# stm32h743.net
KiCad netlist of a schematic drawn in Altium Designer
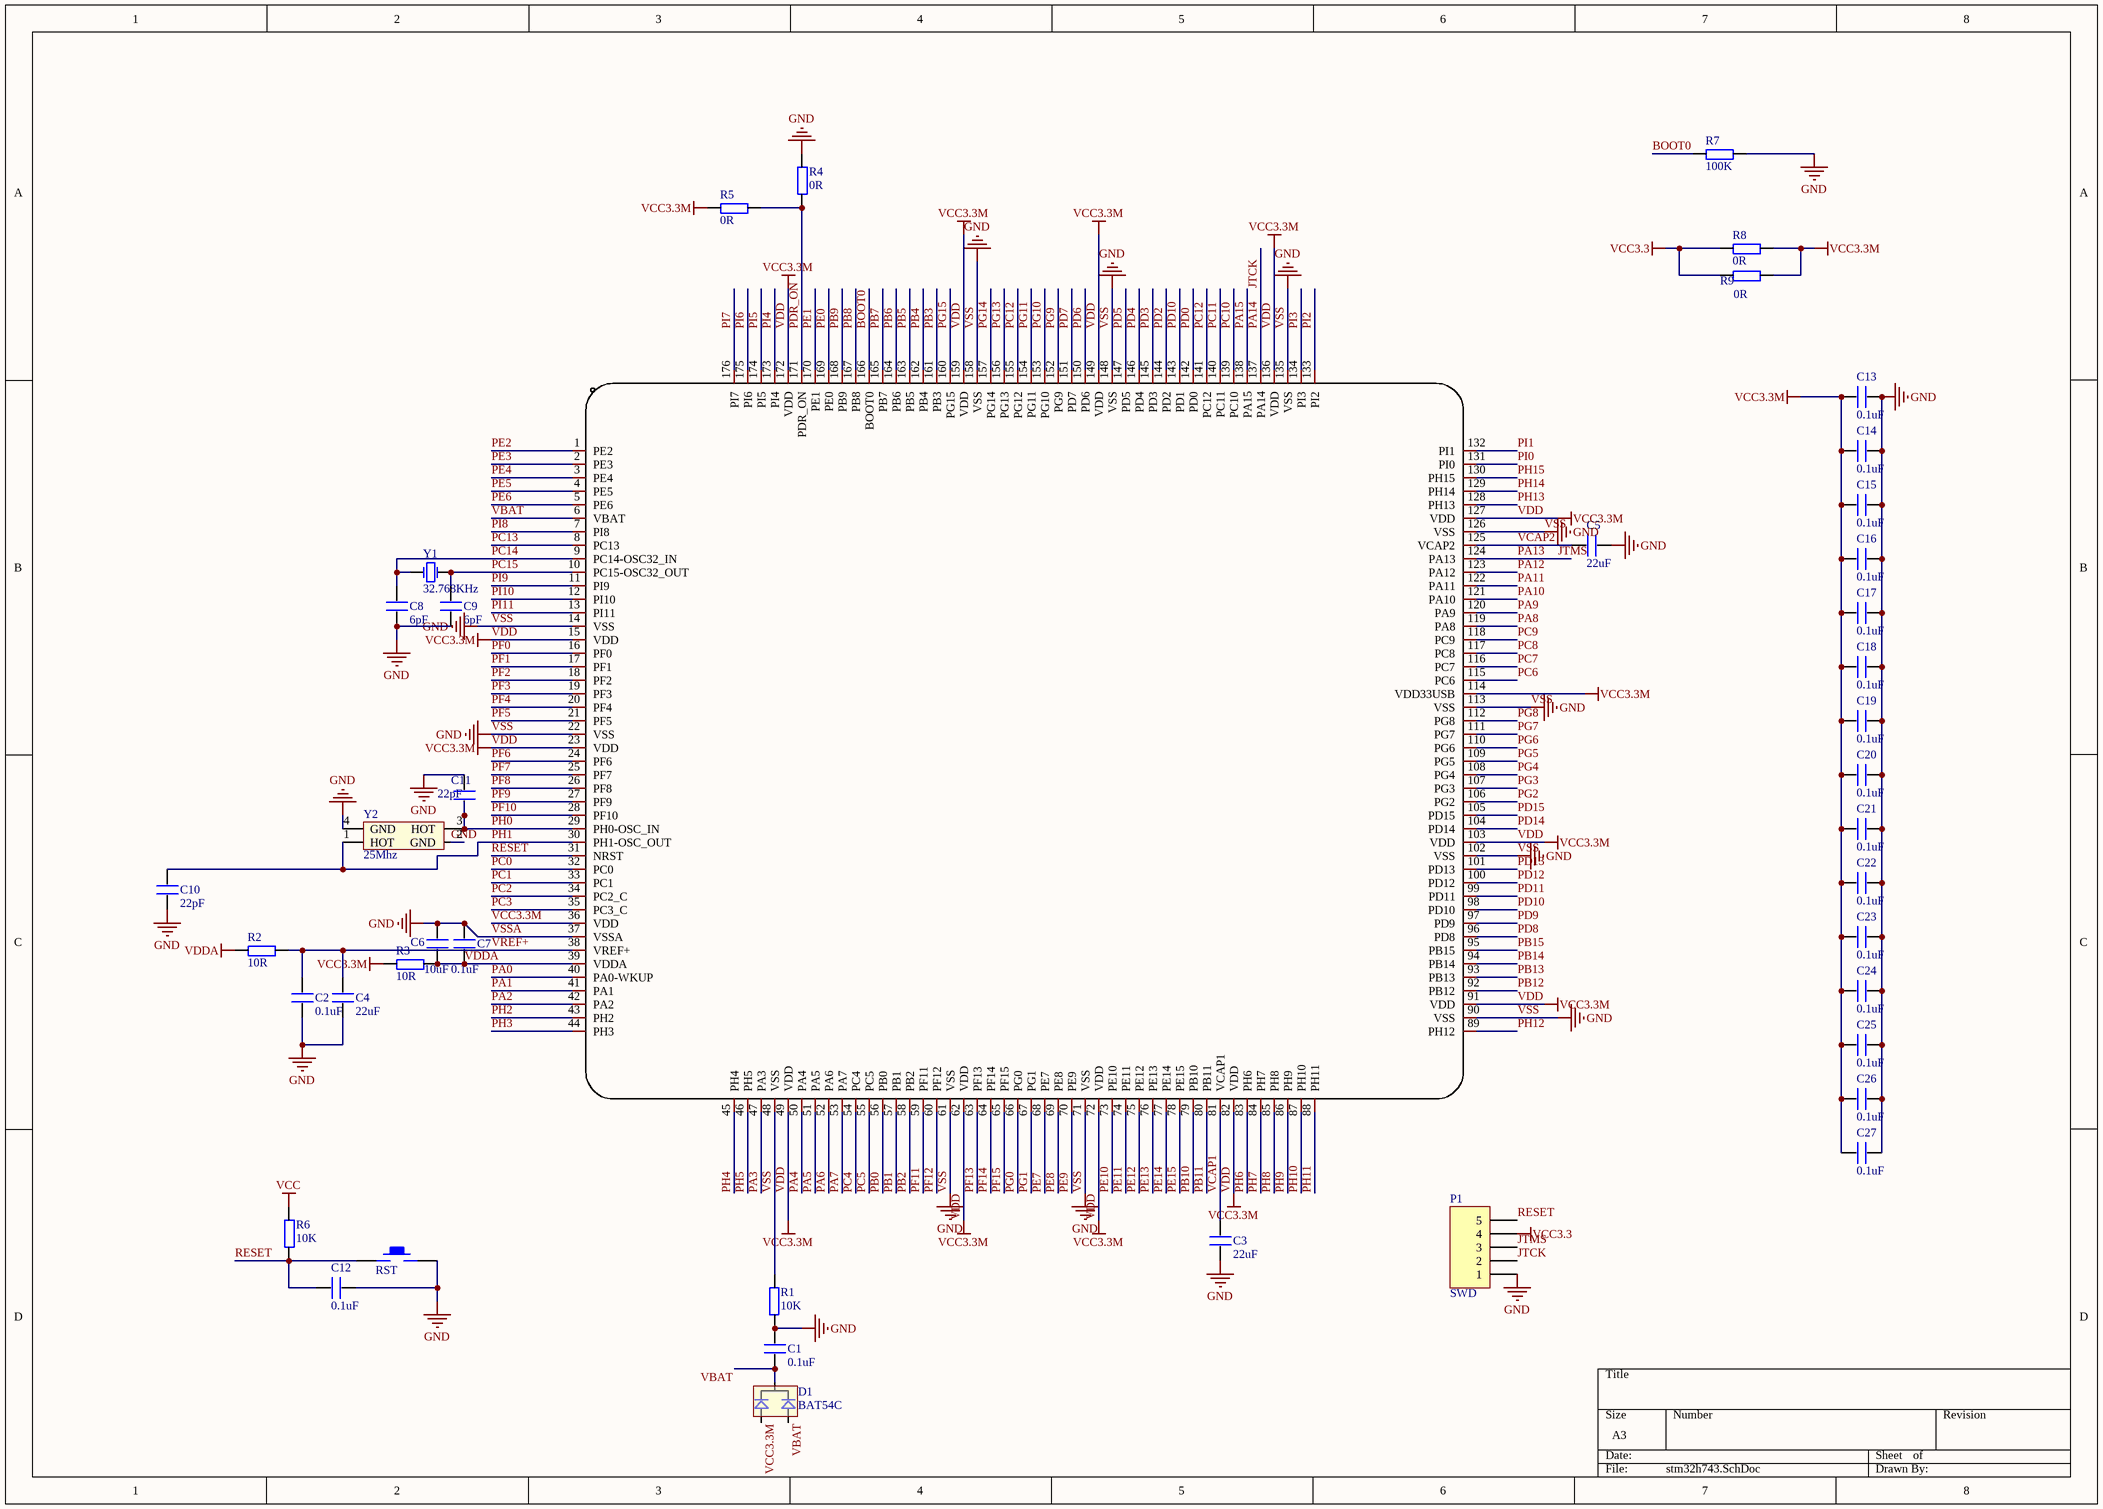
[diagram p0: stm32h743.SchDoc]

(export (version "E")
  (design (tool "Eeschema 10.0.6"))
  (components
    (comp (ref "C1") (value "0.1uF") (footprint "0402") (libsource (lib "STM32H743核心板封装库") (part "C")))
    (comp (ref "C2") (value "0.1uF") (footprint "0402") (libsource (lib "STM32H743核心板封装库") (part "C")))
    (comp (ref "C3") (value "22uF") (footprint "0402") (libsource (lib "STM32H743核心板封装库") (part "C")))
    (comp (ref "C4") (value "22uF") (footprint "0402") (libsource (lib "STM32H743核心板封装库") (part "C")))
    (comp (ref "C5") (value "22uF") (footprint "0402") (libsource (lib "STM32H743核心板封装库") (part "C")))
    (comp (ref "C6") (value "10uF") (footprint "0402") (libsource (lib "STM32H743核心板封装库") (part "C")))
    (comp (ref "C7") (value "0.1uF") (footprint "0402") (libsource (lib "STM32H743核心板封装库") (part "C")))
    (comp (ref "C8") (value "6pF") (footprint "0402") (libsource (lib "STM32H743核心板封装库") (part "C_7")))
    (comp (ref "C9") (value "6pF") (footprint "0402") (libsource (lib "STM32H743核心板封装库") (part "C_7")))
    (comp (ref "C10") (value "22pF") (footprint "0402") (libsource (lib "STM32H743核心板封装库") (part "C")))
    (comp (ref "C11") (value "22pF") (footprint "0402") (libsource (lib "STM32H743核心板封装库") (part "C")))
    (comp (ref "C12") (value "0.1uF") (footprint "0402") (libsource (lib "STM32H743核心板封装库") (part "C")))
    (comp (ref "C13") (value "0.1uF") (footprint "0402") (libsource (lib "STM32H743核心板封装库") (part "C")))
    (comp (ref "C14") (value "0.1uF") (footprint "0402") (libsource (lib "STM32H743核心板封装库") (part "C")))
    (comp (ref "C15") (value "0.1uF") (footprint "0402") (libsource (lib "STM32H743核心板封装库") (part "C")))
    (comp (ref "C16") (value "0.1uF") (footprint "0402") (libsource (lib "STM32H743核心板封装库") (part "C")))
    (comp (ref "C17") (value "0.1uF") (footprint "0402") (libsource (lib "STM32H743核心板封装库") (part "C")))
    (comp (ref "C18") (value "0.1uF") (footprint "0402") (libsource (lib "STM32H743核心板封装库") (part "C")))
    (comp (ref "C19") (value "0.1uF") (footprint "0402") (libsource (lib "STM32H743核心板封装库") (part "C")))
    (comp (ref "C20") (value "0.1uF") (footprint "0402") (libsource (lib "STM32H743核心板封装库") (part "C")))
    (comp (ref "C21") (value "0.1uF") (footprint "0402") (libsource (lib "STM32H743核心板封装库") (part "C")))
    (comp (ref "C22") (value "0.1uF") (footprint "0402") (libsource (lib "STM32H743核心板封装库") (part "C")))
    (comp (ref "C23") (value "0.1uF") (footprint "0402") (libsource (lib "STM32H743核心板封装库") (part "C")))
    (comp (ref "C24") (value "0.1uF") (footprint "0402") (libsource (lib "STM32H743核心板封装库") (part "C")))
    (comp (ref "C25") (value "0.1uF") (footprint "0402") (libsource (lib "STM32H743核心板封装库") (part "C")))
    (comp (ref "C26") (value "0.1uF") (footprint "0402") (libsource (lib "STM32H743核心板封装库") (part "C")))
    (comp (ref "C27") (value "0.1uF") (footprint "0402") (libsource (lib "STM32H743核心板封装库") (part "C")))
    (comp (ref "D1")
      (value "BAT54C")
      (footprint "SOT-23")
      (description "双肖特基二极管")
      (libsource (lib "STM32H743核心板封装库") (part "BAT54C"))
    )
    (comp (ref "P1")
      (value "SWD")
      (footprint "HDR1X5")
      (description "Header, 5-Pin")
      (fields (field (name "PUBLISHER") "Altium Limited"))
      (libsource (lib "STM32H743核心板封装库") (part "Header 5"))
    )
    (comp (ref "R1") (value "10K") (footprint "0402") (libsource (lib "STM32H743核心板封装库") (part "R")))
    (comp (ref "R2") (value "10R") (footprint "0402") (libsource (lib "STM32H743核心板封装库") (part "R")))
    (comp (ref "R3") (value "10R") (footprint "0402") (libsource (lib "STM32H743核心板封装库") (part "R")))
    (comp (ref "R4") (value "0R") (footprint "0402") (libsource (lib "STM32H743核心板封装库") (part "R")))
    (comp (ref "R5") (value "0R") (footprint "0402") (libsource (lib "STM32H743核心板封装库") (part "R")))
    (comp (ref "R6") (value "10K") (footprint "0402") (libsource (lib "STM32H743核心板封装库") (part "R")))
    (comp (ref "R7") (value "100K") (footprint "0402") (libsource (lib "STM32H743核心板封装库") (part "R")))
    (comp (ref "R8") (value "0R") (footprint "0402") (libsource (lib "STM32H743核心板封装库") (part "R")))
    (comp (ref "R9") (value "0R") (footprint "0402") (libsource (lib "STM32H743核心板封装库") (part "R")))
    (comp (ref "RST")
      (value "KEY_M")
      (footprint "KEY_SOP324225")
      (libsource (lib "STM32H743核心板封装库") (part "KEY_M"))
    )
    (comp (ref "U1")
      (value "STM32H743IIT6")
      (footprint "LQFP176")
      (fields (field (name "MANUFACTURER") "ST(意法半导体)"))
      (libsource (lib "altium-import") (part "root_0_STM32H743IIT6_"))
    )
    (comp (ref "Y1")
      (value "32.768KHz")
      (footprint "XTAL3215")
      (description "普通晶振")
      (fields (field (name "PUBLISHER") "Altium Limited"))
      (libsource (lib "STM32H743核心板封装库") (part "XTAL"))
    )
    (comp (ref "Y2")
      (value "25Mhz")
      (footprint "XTAL3225")
      (description "3225贴片无源晶振")
      (libsource (lib "STM32H743核心板封装库") (part "XTAL_3225"))
    )
  )
  (nets
    (net (code "1") (name "/BOOT0") (class "Default")
      (node (ref "R7") (pin "1") (pintype "passive"))
      (node (ref "U1") (pin "166") (pinfunction "BOOT0_166") (pintype "passive"))
    )
    (net (code "2") (name "/JTCK") (class "Default")
      (node (ref "P1") (pin "2") (pinfunction "2_2") (pintype "passive"))
      (node (ref "U1") (pin "137") (pinfunction "PA14_137") (pintype "passive"))
    )
    (net (code "3") (name "/JTMS") (class "Default")
      (node (ref "P1") (pin "3") (pinfunction "3_3") (pintype "passive"))
      (node (ref "U1") (pin "124") (pinfunction "PA13_124") (pintype "passive"))
    )
    (net (code "4") (name "/PA0") (class "Default")
      (node (ref "U1") (pin "40") (pinfunction "PA0-WKUP_40") (pintype "passive"))
    )
    (net (code "5") (name "/PA1") (class "Default")
      (node (ref "U1") (pin "41") (pinfunction "PA1_41") (pintype "passive"))
    )
    (net (code "6") (name "/PA2") (class "Default")
      (node (ref "U1") (pin "42") (pinfunction "PA2_42") (pintype "passive"))
    )
    (net (code "7") (name "/PA3") (class "Default")
      (node (ref "U1") (pin "47") (pinfunction "PA3_47") (pintype "passive"))
    )
    (net (code "8") (name "/PA4") (class "Default")
      (node (ref "U1") (pin "50") (pinfunction "PA4_50") (pintype "passive"))
    )
    (net (code "9") (name "/PA5") (class "Default")
      (node (ref "U1") (pin "51") (pinfunction "PA5_51") (pintype "passive"))
    )
    (net (code "10") (name "/PA6") (class "Default")
      (node (ref "U1") (pin "52") (pinfunction "PA6_52") (pintype "passive"))
    )
    (net (code "11") (name "/PA7") (class "Default")
      (node (ref "U1") (pin "53") (pinfunction "PA7_53") (pintype "passive"))
    )
    (net (code "12") (name "/PA8") (class "Default")
      (node (ref "U1") (pin "119") (pinfunction "PA8_119") (pintype "passive"))
    )
    (net (code "13") (name "/PA9") (class "Default")
      (node (ref "U1") (pin "120") (pinfunction "PA9_120") (pintype "passive"))
    )
    (net (code "14") (name "/PA10") (class "Default")
      (node (ref "U1") (pin "121") (pinfunction "PA10_121") (pintype "passive"))
    )
    (net (code "15") (name "/PA11") (class "Default")
      (node (ref "U1") (pin "122") (pinfunction "PA11_122") (pintype "passive"))
    )
    (net (code "16") (name "/PA12") (class "Default")
      (node (ref "U1") (pin "123") (pinfunction "PA12_123") (pintype "passive"))
    )
    (net (code "17") (name "/PA15") (class "Default")
      (node (ref "U1") (pin "138") (pinfunction "PA15_138") (pintype "passive"))
    )
    (net (code "18") (name "/PB0") (class "Default")
      (node (ref "U1") (pin "56") (pinfunction "PB0_56") (pintype "passive"))
    )
    (net (code "19") (name "/PB1") (class "Default")
      (node (ref "U1") (pin "57") (pinfunction "PB1_57") (pintype "passive"))
    )
    (net (code "20") (name "/PB2") (class "Default")
      (node (ref "U1") (pin "58") (pinfunction "PB2_58") (pintype "passive"))
    )
    (net (code "21") (name "/PB3") (class "Default")
      (node (ref "U1") (pin "161") (pinfunction "PB3_161") (pintype "passive"))
    )
    (net (code "22") (name "/PB4") (class "Default")
      (node (ref "U1") (pin "162") (pinfunction "PB4_162") (pintype "passive"))
    )
    (net (code "23") (name "/PB5") (class "Default")
      (node (ref "U1") (pin "163") (pinfunction "PB5_163") (pintype "passive"))
    )
    (net (code "24") (name "/PB6") (class "Default")
      (node (ref "U1") (pin "164") (pinfunction "PB6_164") (pintype "passive"))
    )
    (net (code "25") (name "/PB7") (class "Default")
      (node (ref "U1") (pin "165") (pinfunction "PB7_165") (pintype "passive"))
    )
    (net (code "26") (name "/PB8") (class "Default")
      (node (ref "U1") (pin "167") (pinfunction "PB8_167") (pintype "passive"))
    )
    (net (code "27") (name "/PB9") (class "Default")
      (node (ref "U1") (pin "168") (pinfunction "PB9_168") (pintype "passive"))
    )
    (net (code "28") (name "/PB10") (class "Default")
      (node (ref "U1") (pin "79") (pinfunction "PB10_79") (pintype "passive"))
    )
    (net (code "29") (name "/PB11") (class "Default")
      (node (ref "U1") (pin "80") (pinfunction "PB11_80") (pintype "passive"))
    )
    (net (code "30") (name "/PB12") (class "Default")
      (node (ref "U1") (pin "92") (pinfunction "PB12_92") (pintype "passive"))
    )
    (net (code "31") (name "/PB13") (class "Default")
      (node (ref "U1") (pin "93") (pinfunction "PB13_93") (pintype "passive"))
    )
    (net (code "32") (name "/PB14") (class "Default")
      (node (ref "U1") (pin "94") (pinfunction "PB14_94") (pintype "passive"))
    )
    (net (code "33") (name "/PB15") (class "Default")
      (node (ref "U1") (pin "95") (pinfunction "PB15_95") (pintype "passive"))
    )
    (net (code "34") (name "/PC0") (class "Default")
      (node (ref "U1") (pin "32") (pinfunction "PC0_32") (pintype "passive"))
    )
    (net (code "35") (name "/PC1") (class "Default")
      (node (ref "U1") (pin "33") (pinfunction "PC1_33") (pintype "passive"))
    )
    (net (code "36") (name "/PC2") (class "Default")
      (node (ref "U1") (pin "34") (pinfunction "PC2_C_34") (pintype "passive"))
    )
    (net (code "37") (name "/PC3") (class "Default")
      (node (ref "U1") (pin "35") (pinfunction "PC3_C_35") (pintype "passive"))
    )
    (net (code "38") (name "/PC4") (class "Default")
      (node (ref "U1") (pin "54") (pinfunction "PC4_54") (pintype "passive"))
    )
    (net (code "39") (name "/PC5") (class "Default")
      (node (ref "U1") (pin "55") (pinfunction "PC5_55") (pintype "passive"))
    )
    (net (code "40") (name "/PC6") (class "Default")
      (node (ref "U1") (pin "115") (pinfunction "PC6_115") (pintype "passive"))
    )
    (net (code "41") (name "/PC7") (class "Default")
      (node (ref "U1") (pin "116") (pinfunction "PC7_116") (pintype "passive"))
    )
    (net (code "42") (name "/PC8") (class "Default")
      (node (ref "U1") (pin "117") (pinfunction "PC8_117") (pintype "passive"))
    )
    (net (code "43") (name "/PC9") (class "Default")
      (node (ref "U1") (pin "118") (pinfunction "PC9_118") (pintype "passive"))
    )
    (net (code "44") (name "/PC10") (class "Default")
      (node (ref "U1") (pin "139") (pinfunction "PC10_139") (pintype "passive"))
    )
    (net (code "45") (name "/PC11") (class "Default")
      (node (ref "U1") (pin "140") (pinfunction "PC11_140") (pintype "passive"))
    )
    (net (code "46") (name "/PC12") (class "Default")
      (node (ref "U1") (pin "141") (pinfunction "PC12_141") (pintype "passive"))
      (node (ref "U1") (pin "155") (pinfunction "PG12_155") (pintype "passive"))
    )
    (net (code "47") (name "/PC13") (class "Default")
      (node (ref "U1") (pin "8") (pinfunction "PC13_8") (pintype "passive"))
    )
    (net (code "48") (name "/PC14") (class "Default")
      (node (ref "C8") (pin "2") (pintype "passive"))
      (node (ref "U1") (pin "9") (pinfunction "PC14-OSC32_IN_9") (pintype "passive"))
      (node (ref "Y1") (pin "1") (pinfunction "OSC1_1") (pintype "passive"))
    )
    (net (code "49") (name "/PC15") (class "Default")
      (node (ref "C9") (pin "2") (pintype "passive"))
      (node (ref "U1") (pin "10") (pinfunction "PC15-OSC32_OUT_10") (pintype "passive"))
      (node (ref "Y1") (pin "2") (pinfunction "OSC2_2") (pintype "passive"))
    )
    (net (code "50") (name "/PD0") (class "Default")
      (node (ref "U1") (pin "142") (pinfunction "PD0_142") (pintype "passive"))
    )
    (net (code "51") (name "/PD2") (class "Default")
      (node (ref "U1") (pin "144") (pinfunction "PD2_144") (pintype "passive"))
    )
    (net (code "52") (name "/PD3") (class "Default")
      (node (ref "U1") (pin "145") (pinfunction "PD3_145") (pintype "passive"))
    )
    (net (code "53") (name "/PD4") (class "Default")
      (node (ref "U1") (pin "146") (pinfunction "PD4_146") (pintype "passive"))
    )
    (net (code "54") (name "/PD5") (class "Default")
      (node (ref "U1") (pin "147") (pinfunction "PD5_147") (pintype "passive"))
    )
    (net (code "55") (name "/PD6") (class "Default")
      (node (ref "U1") (pin "150") (pinfunction "PD6_150") (pintype "passive"))
    )
    (net (code "56") (name "/PD7") (class "Default")
      (node (ref "U1") (pin "151") (pinfunction "PD7_151") (pintype "passive"))
    )
    (net (code "57") (name "/PD8") (class "Default")
      (node (ref "U1") (pin "96") (pinfunction "PD8_96") (pintype "passive"))
    )
    (net (code "58") (name "/PD9") (class "Default")
      (node (ref "U1") (pin "97") (pinfunction "PD9_97") (pintype "passive"))
    )
    (net (code "59") (name "/PD10") (class "Default")
      (node (ref "U1") (pin "143") (pinfunction "PD1_143") (pintype "passive"))
      (node (ref "U1") (pin "98") (pinfunction "PD10_98") (pintype "passive"))
    )
    (net (code "60") (name "/PD11") (class "Default")
      (node (ref "U1") (pin "99") (pinfunction "PD11_99") (pintype "passive"))
    )
    (net (code "61") (name "/PD12") (class "Default")
      (node (ref "U1") (pin "100") (pinfunction "PD12_100") (pintype "passive"))
    )
    (net (code "62") (name "/PD13") (class "Default")
      (node (ref "U1") (pin "101") (pinfunction "PD13_101") (pintype "passive"))
    )
    (net (code "63") (name "/PD14") (class "Default")
      (node (ref "U1") (pin "104") (pinfunction "PD14_104") (pintype "passive"))
    )
    (net (code "64") (name "/PD15") (class "Default")
      (node (ref "U1") (pin "105") (pinfunction "PD15_105") (pintype "passive"))
    )
    (net (code "65") (name "/PDR_ON") (class "Default")
      (node (ref "R4") (pin "1") (pintype "passive"))
      (node (ref "R5") (pin "2") (pintype "passive"))
      (node (ref "U1") (pin "171") (pinfunction "PDR_ON_171") (pintype "passive"))
    )
    (net (code "66") (name "/PE0") (class "Default")
      (node (ref "U1") (pin "169") (pinfunction "PE0_169") (pintype "passive"))
    )
    (net (code "67") (name "/PE1") (class "Default")
      (node (ref "U1") (pin "170") (pinfunction "PE1_170") (pintype "passive"))
    )
    (net (code "68") (name "/PE2") (class "Default")
      (node (ref "U1") (pin "1") (pinfunction "PE2_1") (pintype "passive"))
    )
    (net (code "69") (name "/PE3") (class "Default")
      (node (ref "U1") (pin "2") (pinfunction "PE3_2") (pintype "passive"))
    )
    (net (code "70") (name "/PE4") (class "Default")
      (node (ref "U1") (pin "3") (pinfunction "PE4_3") (pintype "passive"))
    )
    (net (code "71") (name "/PE5") (class "Default")
      (node (ref "U1") (pin "4") (pinfunction "PE5_4") (pintype "passive"))
    )
    (net (code "72") (name "/PE6") (class "Default")
      (node (ref "U1") (pin "5") (pinfunction "PE6_5") (pintype "passive"))
    )
    (net (code "73") (name "/PE7") (class "Default")
      (node (ref "U1") (pin "68") (pinfunction "PE7_68") (pintype "passive"))
    )
    (net (code "74") (name "/PE8") (class "Default")
      (node (ref "U1") (pin "69") (pinfunction "PE8_69") (pintype "passive"))
    )
    (net (code "75") (name "/PE9") (class "Default")
      (node (ref "U1") (pin "70") (pinfunction "PE9_70") (pintype "passive"))
    )
    (net (code "76") (name "/PE10") (class "Default")
      (node (ref "U1") (pin "73") (pinfunction "PE10_73") (pintype "passive"))
    )
    (net (code "77") (name "/PE11") (class "Default")
      (node (ref "U1") (pin "74") (pinfunction "PE11_74") (pintype "passive"))
    )
    (net (code "78") (name "/PE12") (class "Default")
      (node (ref "U1") (pin "75") (pinfunction "PE12_75") (pintype "passive"))
    )
    (net (code "79") (name "/PE13") (class "Default")
      (node (ref "U1") (pin "76") (pinfunction "PE13_76") (pintype "passive"))
    )
    (net (code "80") (name "/PE14") (class "Default")
      (node (ref "U1") (pin "77") (pinfunction "PE14_77") (pintype "passive"))
    )
    (net (code "81") (name "/PE15") (class "Default")
      (node (ref "U1") (pin "78") (pinfunction "PE15_78") (pintype "passive"))
    )
    (net (code "82") (name "/PF0") (class "Default")
      (node (ref "U1") (pin "16") (pinfunction "PF0_16") (pintype "passive"))
    )
    (net (code "83") (name "/PF1") (class "Default")
      (node (ref "U1") (pin "17") (pinfunction "PF1_17") (pintype "passive"))
    )
    (net (code "84") (name "/PF2") (class "Default")
      (node (ref "U1") (pin "18") (pinfunction "PF2_18") (pintype "passive"))
    )
    (net (code "85") (name "/PF3") (class "Default")
      (node (ref "U1") (pin "19") (pinfunction "PF3_19") (pintype "passive"))
    )
    (net (code "86") (name "/PF4") (class "Default")
      (node (ref "U1") (pin "20") (pinfunction "PF4_20") (pintype "passive"))
    )
    (net (code "87") (name "/PF5") (class "Default")
      (node (ref "U1") (pin "21") (pinfunction "PF5_21") (pintype "passive"))
    )
    (net (code "88") (name "/PF6") (class "Default")
      (node (ref "U1") (pin "24") (pinfunction "PF6_24") (pintype "passive"))
    )
    (net (code "89") (name "/PF7") (class "Default")
      (node (ref "U1") (pin "25") (pinfunction "PF7_25") (pintype "passive"))
    )
    (net (code "90") (name "/PF8") (class "Default")
      (node (ref "U1") (pin "26") (pinfunction "PF8_26") (pintype "passive"))
    )
    (net (code "91") (name "/PF9") (class "Default")
      (node (ref "U1") (pin "27") (pinfunction "PF9_27") (pintype "passive"))
    )
    (net (code "92") (name "/PF10") (class "Default")
      (node (ref "U1") (pin "28") (pinfunction "PF10_28") (pintype "passive"))
    )
    (net (code "93") (name "/PF11") (class "Default")
      (node (ref "U1") (pin "59") (pinfunction "PF11_59") (pintype "passive"))
    )
    (net (code "94") (name "/PF12") (class "Default")
      (node (ref "U1") (pin "60") (pinfunction "PF12_60") (pintype "passive"))
    )
    (net (code "95") (name "/PF13") (class "Default")
      (node (ref "U1") (pin "63") (pinfunction "PF13_63") (pintype "passive"))
    )
    (net (code "96") (name "/PF14") (class "Default")
      (node (ref "U1") (pin "64") (pinfunction "PF14_64") (pintype "passive"))
    )
    (net (code "97") (name "/PF15") (class "Default")
      (node (ref "U1") (pin "65") (pinfunction "PF15_65") (pintype "passive"))
    )
    (net (code "98") (name "/PG0") (class "Default")
      (node (ref "U1") (pin "66") (pinfunction "PG0_66") (pintype "passive"))
    )
    (net (code "99") (name "/PG1") (class "Default")
      (node (ref "U1") (pin "67") (pinfunction "PG1_67") (pintype "passive"))
    )
    (net (code "100") (name "/PG2") (class "Default")
      (node (ref "U1") (pin "106") (pinfunction "PG2_106") (pintype "passive"))
    )
    (net (code "101") (name "/PG3") (class "Default")
      (node (ref "U1") (pin "107") (pinfunction "PG3_107") (pintype "passive"))
    )
    (net (code "102") (name "/PG4") (class "Default")
      (node (ref "U1") (pin "108") (pinfunction "PG4_108") (pintype "passive"))
    )
    (net (code "103") (name "/PG5") (class "Default")
      (node (ref "U1") (pin "109") (pinfunction "PG5_109") (pintype "passive"))
    )
    (net (code "104") (name "/PG6") (class "Default")
      (node (ref "U1") (pin "110") (pinfunction "PG6_110") (pintype "passive"))
    )
    (net (code "105") (name "/PG7") (class "Default")
      (node (ref "U1") (pin "111") (pinfunction "PG7_111") (pintype "passive"))
    )
    (net (code "106") (name "/PG8") (class "Default")
      (node (ref "U1") (pin "112") (pinfunction "PG8_112") (pintype "passive"))
    )
    (net (code "107") (name "/PG9") (class "Default")
      (node (ref "U1") (pin "152") (pinfunction "PG9_152") (pintype "passive"))
    )
    (net (code "108") (name "/PG10") (class "Default")
      (node (ref "U1") (pin "153") (pinfunction "PG10_153") (pintype "passive"))
    )
    (net (code "109") (name "/PG11") (class "Default")
      (node (ref "U1") (pin "154") (pinfunction "PG11_154") (pintype "passive"))
    )
    (net (code "110") (name "/PG13") (class "Default")
      (node (ref "U1") (pin "156") (pinfunction "PG13_156") (pintype "passive"))
    )
    (net (code "111") (name "/PG14") (class "Default")
      (node (ref "U1") (pin "157") (pinfunction "PG14_157") (pintype "passive"))
    )
    (net (code "112") (name "/PG15") (class "Default")
      (node (ref "U1") (pin "160") (pinfunction "PG15_160") (pintype "passive"))
    )
    (net (code "113") (name "/PH0") (class "Default")
      (node (ref "C11") (pin "2") (pintype "passive"))
      (node (ref "U1") (pin "29") (pinfunction "PH0-OSC_IN_29") (pintype "passive"))
      (node (ref "Y2") (pin "3") (pinfunction "HOT_3") (pintype "passive"))
    )
    (net (code "114") (name "/PH1") (class "Default")
      (node (ref "C10") (pin "2") (pintype "passive"))
      (node (ref "U1") (pin "30") (pinfunction "PH1-OSC_OUT_30") (pintype "passive"))
      (node (ref "Y2") (pin "1") (pinfunction "HOT_1") (pintype "passive"))
    )
    (net (code "115") (name "/PH2") (class "Default")
      (node (ref "U1") (pin "43") (pinfunction "PH2_43") (pintype "passive"))
    )
    (net (code "116") (name "/PH3") (class "Default")
      (node (ref "U1") (pin "44") (pinfunction "PH3_44") (pintype "passive"))
    )
    (net (code "117") (name "/PH4") (class "Default")
      (node (ref "U1") (pin "45") (pinfunction "PH4_45") (pintype "passive"))
    )
    (net (code "118") (name "/PH5") (class "Default")
      (node (ref "U1") (pin "46") (pinfunction "PH5_46") (pintype "passive"))
    )
    (net (code "119") (name "/PH6") (class "Default")
      (node (ref "U1") (pin "83") (pinfunction "PH6_83") (pintype "passive"))
    )
    (net (code "120") (name "/PH7") (class "Default")
      (node (ref "U1") (pin "84") (pinfunction "PH7_84") (pintype "passive"))
    )
    (net (code "121") (name "/PH8") (class "Default")
      (node (ref "U1") (pin "85") (pinfunction "PH8_85") (pintype "passive"))
    )
    (net (code "122") (name "/PH9") (class "Default")
      (node (ref "U1") (pin "86") (pinfunction "PH9_86") (pintype "passive"))
    )
    (net (code "123") (name "/PH10") (class "Default")
      (node (ref "U1") (pin "87") (pinfunction "PH10_87") (pintype "passive"))
    )
    (net (code "124") (name "/PH11") (class "Default")
      (node (ref "U1") (pin "88") (pinfunction "PH11_88") (pintype "passive"))
    )
    (net (code "125") (name "/PH12") (class "Default")
      (node (ref "U1") (pin "89") (pinfunction "PH12_89") (pintype "passive"))
    )
    (net (code "126") (name "/PH13") (class "Default")
      (node (ref "U1") (pin "128") (pinfunction "PH13_128") (pintype "passive"))
    )
    (net (code "127") (name "/PH14") (class "Default")
      (node (ref "U1") (pin "129") (pinfunction "PH14_129") (pintype "passive"))
    )
    (net (code "128") (name "/PH15") (class "Default")
      (node (ref "U1") (pin "130") (pinfunction "PH15_130") (pintype "passive"))
    )
    (net (code "129") (name "/PI0") (class "Default")
      (node (ref "U1") (pin "131") (pinfunction "PI0_131") (pintype "passive"))
    )
    (net (code "130") (name "/PI1") (class "Default")
      (node (ref "U1") (pin "132") (pinfunction "PI1_132") (pintype "passive"))
    )
    (net (code "131") (name "/PI2") (class "Default")
      (node (ref "U1") (pin "133") (pinfunction "PI2_133") (pintype "passive"))
    )
    (net (code "132") (name "/PI3") (class "Default")
      (node (ref "U1") (pin "134") (pinfunction "PI3_134") (pintype "passive"))
    )
    (net (code "133") (name "/PI4") (class "Default")
      (node (ref "U1") (pin "173") (pinfunction "PI4_173") (pintype "passive"))
    )
    (net (code "134") (name "/PI5") (class "Default")
      (node (ref "U1") (pin "174") (pinfunction "PI5_174") (pintype "passive"))
    )
    (net (code "135") (name "/PI6") (class "Default")
      (node (ref "U1") (pin "175") (pinfunction "PI6_175") (pintype "passive"))
    )
    (net (code "136") (name "/PI7") (class "Default")
      (node (ref "U1") (pin "176") (pinfunction "PI7_176") (pintype "passive"))
    )
    (net (code "137") (name "/PI8") (class "Default")
      (node (ref "U1") (pin "7") (pinfunction "PI8_7") (pintype "passive"))
    )
    (net (code "138") (name "/PI9") (class "Default")
      (node (ref "U1") (pin "11") (pinfunction "PI9_11") (pintype "passive"))
    )
    (net (code "139") (name "/PI10") (class "Default")
      (node (ref "U1") (pin "12") (pinfunction "PI10_12") (pintype "passive"))
    )
    (net (code "140") (name "/PI11") (class "Default")
      (node (ref "U1") (pin "13") (pinfunction "PI11_13") (pintype "passive"))
    )
    (net (code "141") (name "/RESET") (class "Default")
      (node (ref "C12") (pin "1") (pintype "passive"))
      (node (ref "P1") (pin "5") (pinfunction "5_5") (pintype "passive"))
      (node (ref "R6") (pin "1") (pintype "passive"))
      (node (ref "RST") (pin "1") (pinfunction "1_1") (pintype "passive"))
      (node (ref "U1") (pin "31") (pinfunction "NRST_31") (pintype "passive"))
    )
    (net (code "142") (name "/VBAT") (class "Default")
      (node (ref "C1") (pin "2") (pintype "passive"))
      (node (ref "D1") (pin "2") (pintype "passive"))
      (node (ref "D1") (pin "3") (pintype "passive"))
      (node (ref "U1") (pin "6") (pinfunction "VBAT_6") (pintype "passive"))
    )
    (net (code "143") (name "/VCAP1") (class "Default")
      (node (ref "C3") (pin "2") (pintype "passive"))
      (node (ref "U1") (pin "81") (pinfunction "VCAP1_81") (pintype "passive"))
    )
    (net (code "144") (name "/VCAP2") (class "Default")
      (node (ref "C5") (pin "1") (pintype "passive"))
      (node (ref "U1") (pin "125") (pinfunction "VCAP2_125") (pintype "passive"))
    )
    (net (code "145") (name "/VREF+") (class "Default")
      (node (ref "C2") (pin "2") (pintype "passive"))
      (node (ref "C4") (pin "2") (pintype "passive"))
      (node (ref "R2") (pin "2") (pintype "passive"))
      (node (ref "U1") (pin "38") (pinfunction "VREF+_38") (pintype "passive"))
    )
    (net (code "146") (name "GND") (class "Default")
      (node (ref "C1") (pin "1") (pintype "passive"))
      (node (ref "C10") (pin "1") (pintype "passive"))
      (node (ref "C11") (pin "1") (pintype "passive"))
      (node (ref "C12") (pin "2") (pintype "passive"))
      (node (ref "C13") (pin "2") (pintype "passive"))
      (node (ref "C14") (pin "2") (pintype "passive"))
      (node (ref "C15") (pin "2") (pintype "passive"))
      (node (ref "C16") (pin "2") (pintype "passive"))
      (node (ref "C17") (pin "2") (pintype "passive"))
      (node (ref "C18") (pin "2") (pintype "passive"))
      (node (ref "C19") (pin "2") (pintype "passive"))
      (node (ref "C2") (pin "1") (pintype "passive"))
      (node (ref "C20") (pin "2") (pintype "passive"))
      (node (ref "C21") (pin "2") (pintype "passive"))
      (node (ref "C22") (pin "2") (pintype "passive"))
      (node (ref "C23") (pin "2") (pintype "passive"))
      (node (ref "C24") (pin "2") (pintype "passive"))
      (node (ref "C25") (pin "2") (pintype "passive"))
      (node (ref "C26") (pin "2") (pintype "passive"))
      (node (ref "C27") (pin "2") (pintype "passive"))
      (node (ref "C3") (pin "1") (pintype "passive"))
      (node (ref "C4") (pin "1") (pintype "passive"))
      (node (ref "C5") (pin "2") (pintype "passive"))
      (node (ref "C6") (pin "2") (pintype "passive"))
      (node (ref "C7") (pin "2") (pintype "passive"))
      (node (ref "C8") (pin "1") (pintype "passive"))
      (node (ref "C9") (pin "1") (pintype "passive"))
      (node (ref "P1") (pin "1") (pinfunction "1_1") (pintype "passive"))
      (node (ref "R1") (pin "1") (pintype "passive"))
      (node (ref "R1") (pin "2") (pintype "passive"))
      (node (ref "R4") (pin "2") (pintype "passive"))
      (node (ref "R7") (pin "2") (pintype "passive"))
      (node (ref "RST") (pin "2") (pinfunction "2_2") (pintype "passive"))
      (node (ref "U1") (pin "102") (pinfunction "VSS_102") (pintype "passive"))
      (node (ref "U1") (pin "113") (pinfunction "VSS_113") (pintype "passive"))
      (node (ref "U1") (pin "126") (pinfunction "VSS_126") (pintype "passive"))
      (node (ref "U1") (pin "135") (pinfunction "VSS_135") (pintype "passive"))
      (node (ref "U1") (pin "14") (pinfunction "VSS_14") (pintype "passive"))
      (node (ref "U1") (pin "148") (pinfunction "VSS_148") (pintype "passive"))
      (node (ref "U1") (pin "158") (pinfunction "VSS_158") (pintype "passive"))
      (node (ref "U1") (pin "22") (pinfunction "VSS_22") (pintype "passive"))
      (node (ref "U1") (pin "37") (pinfunction "VSSA_37") (pintype "passive"))
      (node (ref "U1") (pin "48") (pinfunction "VSS_48") (pintype "passive"))
      (node (ref "U1") (pin "61") (pinfunction "VSS_61") (pintype "passive"))
      (node (ref "U1") (pin "71") (pinfunction "VSS_71") (pintype "passive"))
      (node (ref "U1") (pin "90") (pinfunction "VSS_90") (pintype "passive"))
      (node (ref "Y2") (pin "2") (pinfunction "GND_2") (pintype "passive"))
      (node (ref "Y2") (pin "4") (pinfunction "GND_4") (pintype "passive"))
    )
    (net (code "147") (name "VCC") (class "Default") (node (ref "R6") (pin "2") (pintype "passive")))
    (net (code "148") (name "VCC3.3") (class "Default")
      (node (ref "P1") (pin "4") (pinfunction "4_4") (pintype "passive"))
      (node (ref "R8") (pin "1") (pintype "passive"))
      (node (ref "R9") (pin "1") (pintype "passive"))
    )
    (net (code "149") (name "VCC3.3M") (class "Default")
      (node (ref "C13") (pin "1") (pintype "passive"))
      (node (ref "C14") (pin "1") (pintype "passive"))
      (node (ref "C15") (pin "1") (pintype "passive"))
      (node (ref "C16") (pin "1") (pintype "passive"))
      (node (ref "C17") (pin "1") (pintype "passive"))
      (node (ref "C18") (pin "1") (pintype "passive"))
      (node (ref "C19") (pin "1") (pintype "passive"))
      (node (ref "C20") (pin "1") (pintype "passive"))
      (node (ref "C21") (pin "1") (pintype "passive"))
      (node (ref "C22") (pin "1") (pintype "passive"))
      (node (ref "C23") (pin "1") (pintype "passive"))
      (node (ref "C24") (pin "1") (pintype "passive"))
      (node (ref "C25") (pin "1") (pintype "passive"))
      (node (ref "C26") (pin "1") (pintype "passive"))
      (node (ref "C27") (pin "1") (pintype "passive"))
      (node (ref "D1") (pin "1") (pintype "passive"))
      (node (ref "R3") (pin "1") (pintype "passive"))
      (node (ref "R5") (pin "1") (pintype "passive"))
      (node (ref "R8") (pin "2") (pintype "passive"))
      (node (ref "R9") (pin "2") (pintype "passive"))
      (node (ref "U1") (pin "103") (pinfunction "VDD_103") (pintype "passive"))
      (node (ref "U1") (pin "114") (pinfunction "VDD33USB_114") (pintype "passive"))
      (node (ref "U1") (pin "127") (pinfunction "VDD_127") (pintype "passive"))
      (node (ref "U1") (pin "136") (pinfunction "VDD_136") (pintype "passive"))
      (node (ref "U1") (pin "149") (pinfunction "VDD_149") (pintype "passive"))
      (node (ref "U1") (pin "15") (pinfunction "VDD_15") (pintype "passive"))
      (node (ref "U1") (pin "159") (pinfunction "VDD_159") (pintype "passive"))
      (node (ref "U1") (pin "172") (pinfunction "VDD_172") (pintype "passive"))
      (node (ref "U1") (pin "23") (pinfunction "VDD_23") (pintype "passive"))
      (node (ref "U1") (pin "36") (pinfunction "VDD_36") (pintype "passive"))
      (node (ref "U1") (pin "49") (pinfunction "VDD_49") (pintype "passive"))
      (node (ref "U1") (pin "62") (pinfunction "VDD_62") (pintype "passive"))
      (node (ref "U1") (pin "72") (pinfunction "VDD_72") (pintype "passive"))
      (node (ref "U1") (pin "82") (pinfunction "VDD_82") (pintype "passive"))
      (node (ref "U1") (pin "91") (pinfunction "VDD_91") (pintype "passive"))
    )
    (net (code "150") (name "VDDA") (class "Default")
      (node (ref "C6") (pin "1") (pintype "passive"))
      (node (ref "C7") (pin "1") (pintype "passive"))
      (node (ref "R2") (pin "1") (pintype "passive"))
      (node (ref "R3") (pin "2") (pintype "passive"))
      (node (ref "U1") (pin "39") (pinfunction "VDDA_39") (pintype "passive"))
    )
  )
)
